# Nostromo_Gamepad.net
KiCad netlist of a schematic drawn in EAGLE
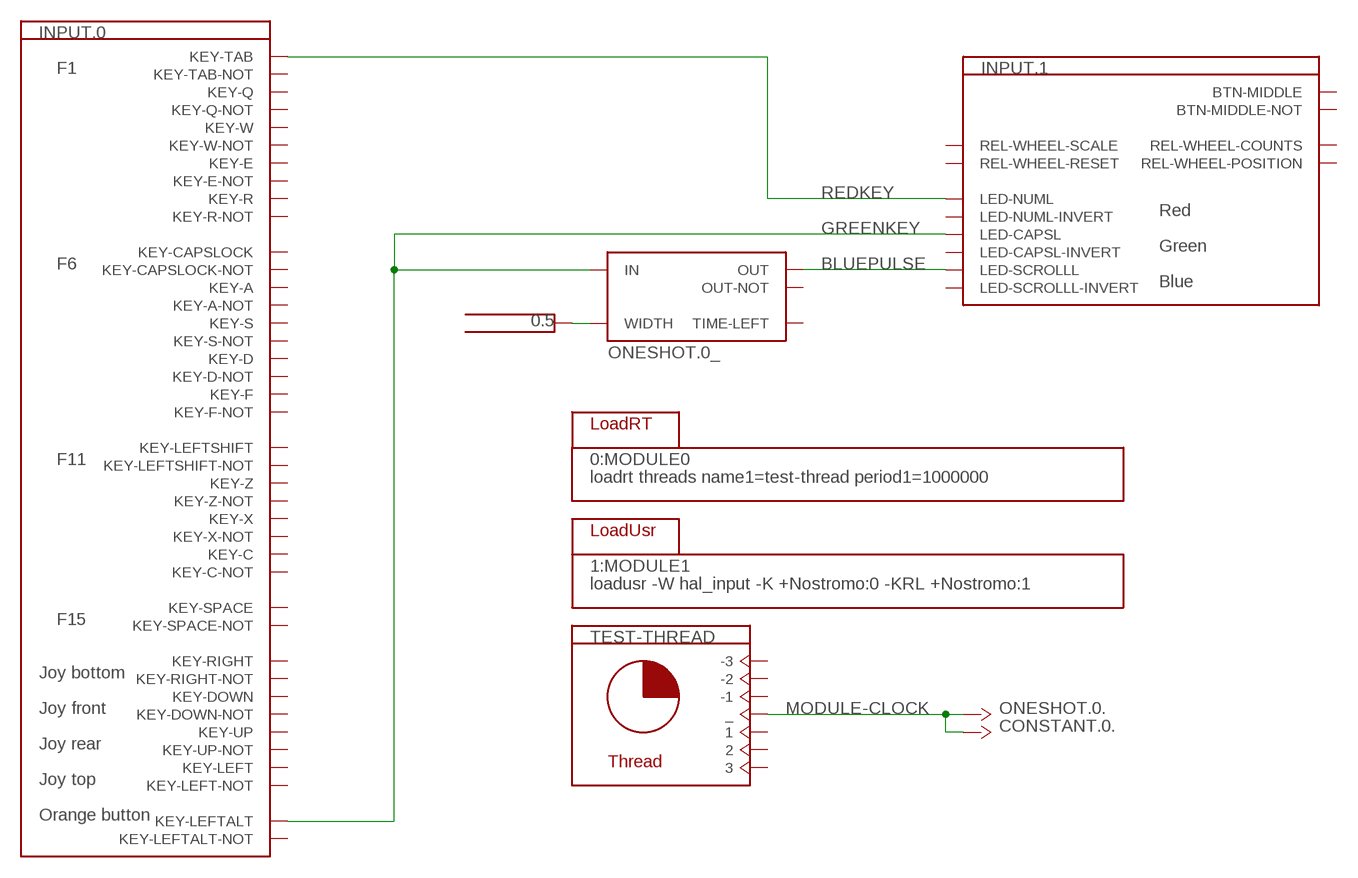
[diagram p0: schematic, sheet 1]

(export (version "E")
  (design (tool "Eeschema 10.0.6"))
  (components
    (comp (ref "0:MODULE0")
      (value "loadrt threads name1=test-thread period1=1000000")
      (footprint "eagle-import:DUMMY")
      (libsource (lib "eagle-import") (part "LOADRT"))
    )
    (comp (ref "CONSTANT.0")
      (value "0.5")
      (footprint "eagle-import:DUMMY")
      (libsource (lib "eagle-import") (part "CONSTANT"))
    )
    (comp (ref "INPUT.0")
      (value "NOSTROMO-N52-KEYS")
      (footprint "eagle-import:DUMMY")
      (libsource (lib "eagle-import") (part "NOSTROMO-N52-KEYS"))
    )
    (comp (ref "INPUT.1")
      (value "NOSTROMO-N52-WHEEL-LEDS")
      (footprint "eagle-import:DUMMY")
      (libsource (lib "eagle-import") (part "NOSTROMO-N52-WHEEL-LEDS"))
    )
    (comp (ref "ONESHOT.0")
      (value "ONESHOT")
      (footprint "eagle-import:DUMMY")
      (libsource (lib "eagle-import") (part "ONESHOT"))
    )
    (comp (ref "TEST-THREAD")
      (value "THREAD")
      (footprint "eagle-import:DUMMY")
      (libsource (lib "eagle-import") (part "THREAD"))
    )
  )
  (nets
    (net (code "1") (name "/BLUEPULSE") (class "Default")
      (node (ref "INPUT.1") (pin "P$7") (pinfunction "LED-SCROLLL_P$7") (pintype "input"))
      (node (ref "ONESHOT.0") (pin "P$6") (pinfunction "OUT_P$6") (pintype "output"))
    )
    (net (code "2") (name "/GREENKEY") (class "Default")
      (node (ref "INPUT.0") (pin "P$18") (pinfunction "KEY-LEFTALT_P$18") (pintype "bidirectional"))
      (node (ref "INPUT.1") (pin "P$3") (pinfunction "LED-CAPSL_P$3") (pintype "input"))
      (node (ref "ONESHOT.0") (pin "P$5") (pinfunction "IN_P$5") (pintype "input"))
    )
    (net (code "3") (name "/MODULE-CLOCK") (class "Default")
      (node (ref "CONSTANT.0") (pin "P$1") (pinfunction "PIN_THREAD_P$1") (pintype "bidirectional"))
      (node (ref "ONESHOT.0") (pin "P$1") (pinfunction "PIN_THREAD_P$1") (pintype "bidirectional"))
      (node (ref "TEST-THREAD") (pin "P$7") (pinfunction "__P$7") (pintype "output"))
    )
    (net (code "4") (name "/REDKEY") (class "Default")
      (node (ref "INPUT.0") (pin "P$32") (pinfunction "KEY-TAB_P$32") (pintype "bidirectional"))
      (node (ref "INPUT.1") (pin "P$5") (pinfunction "LED-NUML_P$5") (pintype "input"))
    )
    (net (code "5") (name "Net-(CONSTANT.0B-OUT)") (class "Default")
      (node (ref "CONSTANT.0") (pin "P$2") (pinfunction "OUT_P$2") (pintype "output"))
      (node (ref "ONESHOT.0") (pin "P$9") (pinfunction "WIDTH_P$9") (pintype "input"))
    )
    (net (code "6") (name "unconnected-(INPUT.0-KEY-A-NOT-PadP$3)") (class "Default")
      (node (ref "INPUT.0") (pin "P$3") (pinfunction "KEY-A-NOT_P$3") (pintype "bidirectional"))
    )
    (net (code "7") (name "unconnected-(INPUT.0-KEY-A-PadP$2)") (class "Default")
      (node (ref "INPUT.0") (pin "P$2") (pinfunction "KEY-A_P$2") (pintype "bidirectional"))
    )
    (net (code "8") (name "unconnected-(INPUT.0-KEY-C-NOT-PadP$5)") (class "Default")
      (node (ref "INPUT.0") (pin "P$5") (pinfunction "KEY-C-NOT_P$5") (pintype "bidirectional"))
    )
    (net (code "9") (name "unconnected-(INPUT.0-KEY-C-PadP$4)") (class "Default")
      (node (ref "INPUT.0") (pin "P$4") (pinfunction "KEY-C_P$4") (pintype "bidirectional"))
    )
    (net (code "10") (name "unconnected-(INPUT.0-KEY-CAPSLOCK-NOT-PadP$7)") (class "Default")
      (node (ref "INPUT.0") (pin "P$7") (pinfunction "KEY-CAPSLOCK-NOT_P$7") (pintype "bidirectional"))
    )
    (net (code "11") (name "unconnected-(INPUT.0-KEY-CAPSLOCK-PadP$6)") (class "Default")
      (node (ref "INPUT.0") (pin "P$6") (pinfunction "KEY-CAPSLOCK_P$6") (pintype "bidirectional"))
    )
    (net (code "12") (name "unconnected-(INPUT.0-KEY-D-NOT-PadP$9)") (class "Default")
      (node (ref "INPUT.0") (pin "P$9") (pinfunction "KEY-D-NOT_P$9") (pintype "bidirectional"))
    )
    (net (code "13") (name "unconnected-(INPUT.0-KEY-D-PadP$8)") (class "Default")
      (node (ref "INPUT.0") (pin "P$8") (pinfunction "KEY-D_P$8") (pintype "bidirectional"))
    )
    (net (code "14") (name "unconnected-(INPUT.0-KEY-DOWN-NOT-PadP$11)") (class "Default")
      (node (ref "INPUT.0") (pin "P$11") (pinfunction "KEY-DOWN-NOT_P$11") (pintype "bidirectional"))
    )
    (net (code "15") (name "unconnected-(INPUT.0-KEY-DOWN-PadP$10)") (class "Default")
      (node (ref "INPUT.0") (pin "P$10") (pinfunction "KEY-DOWN_P$10") (pintype "bidirectional"))
    )
    (net (code "16") (name "unconnected-(INPUT.0-KEY-E-NOT-PadP$13)") (class "Default")
      (node (ref "INPUT.0") (pin "P$13") (pinfunction "KEY-E-NOT_P$13") (pintype "bidirectional"))
    )
    (net (code "17") (name "unconnected-(INPUT.0-KEY-E-PadP$12)") (class "Default")
      (node (ref "INPUT.0") (pin "P$12") (pinfunction "KEY-E_P$12") (pintype "bidirectional"))
    )
    (net (code "18") (name "unconnected-(INPUT.0-KEY-F-NOT-PadP$15)") (class "Default")
      (node (ref "INPUT.0") (pin "P$15") (pinfunction "KEY-F-NOT_P$15") (pintype "bidirectional"))
    )
    (net (code "19") (name "unconnected-(INPUT.0-KEY-F-PadP$14)") (class "Default")
      (node (ref "INPUT.0") (pin "P$14") (pinfunction "KEY-F_P$14") (pintype "bidirectional"))
    )
    (net (code "20") (name "unconnected-(INPUT.0-KEY-LEFT-NOT-PadP$17)") (class "Default")
      (node (ref "INPUT.0") (pin "P$17") (pinfunction "KEY-LEFT-NOT_P$17") (pintype "bidirectional"))
    )
    (net (code "21") (name "unconnected-(INPUT.0-KEY-LEFT-PadP$16)") (class "Default")
      (node (ref "INPUT.0") (pin "P$16") (pinfunction "KEY-LEFT_P$16") (pintype "bidirectional"))
    )
    (net (code "22") (name "unconnected-(INPUT.0-KEY-LEFTALT-NOT-PadP$19)") (class "Default")
      (node (ref "INPUT.0") (pin "P$19") (pinfunction "KEY-LEFTALT-NOT_P$19") (pintype "bidirectional"))
    )
    (net (code "23") (name "unconnected-(INPUT.0-KEY-LEFTSHIFT-NOT-PadP$21)") (class "Default")
      (node (ref "INPUT.0") (pin "P$21") (pinfunction "KEY-LEFTSHIFT-NOT_P$21") (pintype "bidirectional"))
    )
    (net (code "24") (name "unconnected-(INPUT.0-KEY-LEFTSHIFT-PadP$20)") (class "Default")
      (node (ref "INPUT.0") (pin "P$20") (pinfunction "KEY-LEFTSHIFT_P$20") (pintype "bidirectional"))
    )
    (net (code "25") (name "unconnected-(INPUT.0-KEY-Q-NOT-PadP$23)") (class "Default")
      (node (ref "INPUT.0") (pin "P$23") (pinfunction "KEY-Q-NOT_P$23") (pintype "bidirectional"))
    )
    (net (code "26") (name "unconnected-(INPUT.0-KEY-Q-PadP$22)") (class "Default")
      (node (ref "INPUT.0") (pin "P$22") (pinfunction "KEY-Q_P$22") (pintype "bidirectional"))
    )
    (net (code "27") (name "unconnected-(INPUT.0-KEY-R-NOT-PadP$25)") (class "Default")
      (node (ref "INPUT.0") (pin "P$25") (pinfunction "KEY-R-NOT_P$25") (pintype "bidirectional"))
    )
    (net (code "28") (name "unconnected-(INPUT.0-KEY-R-PadP$24)") (class "Default")
      (node (ref "INPUT.0") (pin "P$24") (pinfunction "KEY-R_P$24") (pintype "bidirectional"))
    )
    (net (code "29") (name "unconnected-(INPUT.0-KEY-RIGHT-NOT-PadP$27)") (class "Default")
      (node (ref "INPUT.0") (pin "P$27") (pinfunction "KEY-RIGHT-NOT_P$27") (pintype "bidirectional"))
    )
    (net (code "30") (name "unconnected-(INPUT.0-KEY-RIGHT-PadP$26)") (class "Default")
      (node (ref "INPUT.0") (pin "P$26") (pinfunction "KEY-RIGHT_P$26") (pintype "bidirectional"))
    )
    (net (code "31") (name "unconnected-(INPUT.0-KEY-S-NOT-PadP$29)") (class "Default")
      (node (ref "INPUT.0") (pin "P$29") (pinfunction "KEY-S-NOT_P$29") (pintype "bidirectional"))
    )
    (net (code "32") (name "unconnected-(INPUT.0-KEY-S-PadP$28)") (class "Default")
      (node (ref "INPUT.0") (pin "P$28") (pinfunction "KEY-S_P$28") (pintype "bidirectional"))
    )
    (net (code "33") (name "unconnected-(INPUT.0-KEY-SPACE-NOT-PadP$31)") (class "Default")
      (node (ref "INPUT.0") (pin "P$31") (pinfunction "KEY-SPACE-NOT_P$31") (pintype "bidirectional"))
    )
    (net (code "34") (name "unconnected-(INPUT.0-KEY-SPACE-PadP$30)") (class "Default")
      (node (ref "INPUT.0") (pin "P$30") (pinfunction "KEY-SPACE_P$30") (pintype "bidirectional"))
    )
    (net (code "35") (name "unconnected-(INPUT.0-KEY-TAB-NOT-PadP$33)") (class "Default")
      (node (ref "INPUT.0") (pin "P$33") (pinfunction "KEY-TAB-NOT_P$33") (pintype "bidirectional"))
    )
    (net (code "36") (name "unconnected-(INPUT.0-KEY-UP-NOT-PadP$35)") (class "Default")
      (node (ref "INPUT.0") (pin "P$35") (pinfunction "KEY-UP-NOT_P$35") (pintype "bidirectional"))
    )
    (net (code "37") (name "unconnected-(INPUT.0-KEY-UP-PadP$34)") (class "Default")
      (node (ref "INPUT.0") (pin "P$34") (pinfunction "KEY-UP_P$34") (pintype "bidirectional"))
    )
    (net (code "38") (name "unconnected-(INPUT.0-KEY-W-NOT-PadP$37)") (class "Default")
      (node (ref "INPUT.0") (pin "P$37") (pinfunction "KEY-W-NOT_P$37") (pintype "bidirectional"))
    )
    (net (code "39") (name "unconnected-(INPUT.0-KEY-W-PadP$36)") (class "Default")
      (node (ref "INPUT.0") (pin "P$36") (pinfunction "KEY-W_P$36") (pintype "bidirectional"))
    )
    (net (code "40") (name "unconnected-(INPUT.0-KEY-X-NOT-PadP$39)") (class "Default")
      (node (ref "INPUT.0") (pin "P$39") (pinfunction "KEY-X-NOT_P$39") (pintype "bidirectional"))
    )
    (net (code "41") (name "unconnected-(INPUT.0-KEY-X-PadP$38)") (class "Default")
      (node (ref "INPUT.0") (pin "P$38") (pinfunction "KEY-X_P$38") (pintype "bidirectional"))
    )
    (net (code "42") (name "unconnected-(INPUT.0-KEY-Z-NOT-PadP$41)") (class "Default")
      (node (ref "INPUT.0") (pin "P$41") (pinfunction "KEY-Z-NOT_P$41") (pintype "bidirectional"))
    )
    (net (code "43") (name "unconnected-(INPUT.0-KEY-Z-PadP$40)") (class "Default")
      (node (ref "INPUT.0") (pin "P$40") (pinfunction "KEY-Z_P$40") (pintype "bidirectional"))
    )
    (net (code "44") (name "unconnected-(INPUT.1-BTN-MIDDLE-NOT-PadP$2)") (class "Default")
      (node (ref "INPUT.1") (pin "P$2") (pinfunction "BTN-MIDDLE-NOT_P$2") (pintype "output"))
    )
    (net (code "45") (name "unconnected-(INPUT.1-BTN-MIDDLE-PadP$1)") (class "Default")
      (node (ref "INPUT.1") (pin "P$1") (pinfunction "BTN-MIDDLE_P$1") (pintype "output"))
    )
    (net (code "46") (name "unconnected-(INPUT.1-LED-CAPSL-INVERT-PadP$4)") (class "Default")
      (node (ref "INPUT.1") (pin "P$4") (pinfunction "LED-CAPSL-INVERT_P$4") (pintype "input"))
    )
    (net (code "47") (name "unconnected-(INPUT.1-LED-NUML-INVERT-PadP$6)") (class "Default")
      (node (ref "INPUT.1") (pin "P$6") (pinfunction "LED-NUML-INVERT_P$6") (pintype "input"))
    )
    (net (code "48") (name "unconnected-(INPUT.1-LED-SCROLLL-INVERT-PadP$8)") (class "Default")
      (node (ref "INPUT.1") (pin "P$8") (pinfunction "LED-SCROLLL-INVERT_P$8") (pintype "input"))
    )
    (net (code "49") (name "unconnected-(INPUT.1-REL-WHEEL-COUNTS-PadP$9)") (class "Default")
      (node (ref "INPUT.1") (pin "P$9") (pinfunction "REL-WHEEL-COUNTS_P$9") (pintype "output"))
    )
    (net (code "50") (name "unconnected-(INPUT.1-REL-WHEEL-POSITION-PadP$10)") (class "Default")
      (node (ref "INPUT.1") (pin "P$10") (pinfunction "REL-WHEEL-POSITION_P$10") (pintype "output"))
    )
    (net (code "51") (name "unconnected-(INPUT.1-REL-WHEEL-RESET-PadP$11)") (class "Default")
      (node (ref "INPUT.1") (pin "P$11") (pinfunction "REL-WHEEL-RESET_P$11") (pintype "input"))
    )
    (net (code "52") (name "unconnected-(INPUT.1-REL-WHEEL-SCALE-PadP$12)") (class "Default")
      (node (ref "INPUT.1") (pin "P$12") (pinfunction "REL-WHEEL-SCALE_P$12") (pintype "input"))
    )
    (net (code "53") (name "unconnected-(ONESHOT.0E-OUT-NOT-PadP$7)") (class "Default")
      (node (ref "ONESHOT.0") (pin "P$7") (pinfunction "OUT-NOT_P$7") (pintype "output"))
    )
    (net (code "54") (name "unconnected-(ONESHOT.0E-TIME-LEFT-PadP$8)") (class "Default")
      (node (ref "ONESHOT.0") (pin "P$8") (pinfunction "TIME-LEFT_P$8") (pintype "output"))
    )
    (net (code "55") (name "unconnected-(TEST-THREAD--1-PadP$1)") (class "Default")
      (node (ref "TEST-THREAD") (pin "P$1") (pinfunction "-1_P$1") (pintype "output"))
    )
    (net (code "56") (name "unconnected-(TEST-THREAD--2-PadP$2)") (class "Default")
      (node (ref "TEST-THREAD") (pin "P$2") (pinfunction "-2_P$2") (pintype "output"))
    )
    (net (code "57") (name "unconnected-(TEST-THREAD--3-PadP$3)") (class "Default")
      (node (ref "TEST-THREAD") (pin "P$3") (pinfunction "-3_P$3") (pintype "output"))
    )
    (net (code "58") (name "unconnected-(TEST-THREAD-1-PadP$4)") (class "Default")
      (node (ref "TEST-THREAD") (pin "P$4") (pinfunction "1_P$4") (pintype "output"))
    )
    (net (code "59") (name "unconnected-(TEST-THREAD-2-PadP$5)") (class "Default")
      (node (ref "TEST-THREAD") (pin "P$5") (pinfunction "2_P$5") (pintype "output"))
    )
    (net (code "60") (name "unconnected-(TEST-THREAD-3-PadP$6)") (class "Default")
      (node (ref "TEST-THREAD") (pin "P$6") (pinfunction "3_P$6") (pintype "output"))
    )
  )
)
